# THAT15xx_lean_GainPot.net
KiCad netlist of a schematic drawn in EAGLE
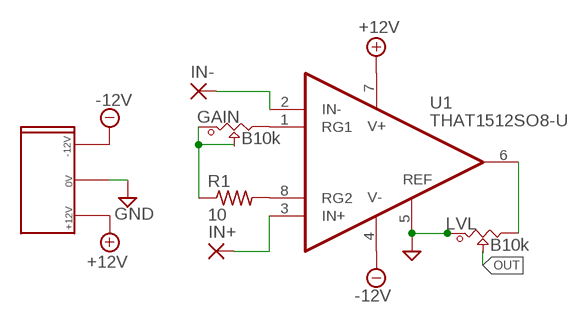
[diagram p0: schematic, sheet 1]

(export (version "E")
  (design (tool "Eeschema 10.0.6"))
  (components
    (comp (ref "GAIN")
      (value "B10k")
      (footprint "eagle-import:POT_9MM_SMD")
      (libsource (lib "eagle-import") (part "POT_9MM_SMD"))
    )
    (comp (ref "IN+")
      (value "WIREPADSMD5-1,8")
      (footprint "eagle-import:5-1,8")
      (libsource (lib "eagle-import") (part "WIREPADSMD5-1,8"))
    )
    (comp (ref "IN-")
      (value "WIREPADSMD5-1,8")
      (footprint "eagle-import:5-1,8")
      (libsource (lib "eagle-import") (part "WIREPADSMD5-1,8"))
    )
    (comp (ref "LVL")
      (value "B10k")
      (footprint "eagle-import:POT_9MM_SMD")
      (libsource (lib "eagle-import") (part "POT_9MM_SMD"))
    )
    (comp (ref "R1")
      (value "10")
      (footprint "eagle-import:R0603")
      (libsource (lib "eagle-import") (part "R-US_R0603"))
    )
    (comp (ref "U$1")
      (value "EURO_POW_CEH")
      (footprint "eagle-import:EURO_POW_CEH")
      (libsource (lib "eagle-import") (part "EURO_POW_CEH"))
    )
    (comp (ref "U1")
      (value "THAT1512SO8-U")
      (footprint "eagle-import:SO08")
      (libsource (lib "eagle-import") (part "THAT1512SO8-U"))
    )
  )
  (nets
    (net (code "1") (name "+12V") (class "Default")
      (node (ref "U$1") (pin "+12V") (pinfunction "+12V_+12V") (pintype "bidirectional"))
      (node (ref "U1") (pin "7") (pinfunction "V+_7") (pintype "power_in"))
    )
    (net (code "2") (name "-12V") (class "Default")
      (node (ref "U$1") (pin "-12V") (pinfunction "-12V_-12V") (pintype "bidirectional"))
      (node (ref "U1") (pin "4") (pinfunction "V-_4") (pintype "power_in"))
    )
    (net (code "3") (name "GND") (class "Default")
      (node (ref "LVL") (pin "1") (pinfunction "1_1") (pintype "bidirectional"))
      (node (ref "U$1") (pin "GND") (pinfunction "GND_GND") (pintype "bidirectional"))
      (node (ref "U1") (pin "5") (pinfunction "REF_5") (pintype "input"))
    )
    (net (code "4") (name "Net-(GAIN-Pad1)") (class "Default")
      (node (ref "GAIN") (pin "1") (pinfunction "1_1") (pintype "bidirectional"))
      (node (ref "GAIN") (pin "2") (pinfunction "2_2") (pintype "bidirectional"))
      (node (ref "R1") (pin "1") (pinfunction "1_1") (pintype "passive"))
    )
    (net (code "5") (name "Net-(IN+-P)") (class "Default")
      (node (ref "IN+") (pin "1") (pinfunction "P_1") (pintype "passive"))
      (node (ref "U1") (pin "3") (pinfunction "IN+_3") (pintype "input"))
    )
    (net (code "6") (name "Net-(IN--P)") (class "Default")
      (node (ref "IN-") (pin "1") (pinfunction "P_1") (pintype "passive"))
      (node (ref "U1") (pin "2") (pinfunction "IN-_2") (pintype "input"))
    )
    (net (code "7") (name "Net-(U1-OUT)") (class "Default")
      (node (ref "LVL") (pin "3") (pinfunction "3_3") (pintype "bidirectional"))
      (node (ref "U1") (pin "6") (pinfunction "OUT_6") (pintype "output"))
    )
    (net (code "8") (name "Net-(U1-RG1)") (class "Default")
      (node (ref "GAIN") (pin "3") (pinfunction "3_3") (pintype "bidirectional"))
      (node (ref "U1") (pin "1") (pinfunction "RG1_1") (pintype "input"))
    )
    (net (code "9") (name "Net-(U1-RG2)") (class "Default")
      (node (ref "R1") (pin "2") (pinfunction "2_2") (pintype "passive"))
      (node (ref "U1") (pin "8") (pinfunction "RG2_8") (pintype "input"))
    )
    (net (code "10") (name "OUT") (class "Default")
      (node (ref "LVL") (pin "2") (pinfunction "2_2") (pintype "bidirectional"))
    )
  )
)
